# SPI.net
KiCad netlist of a schematic drawn in Altium Designer
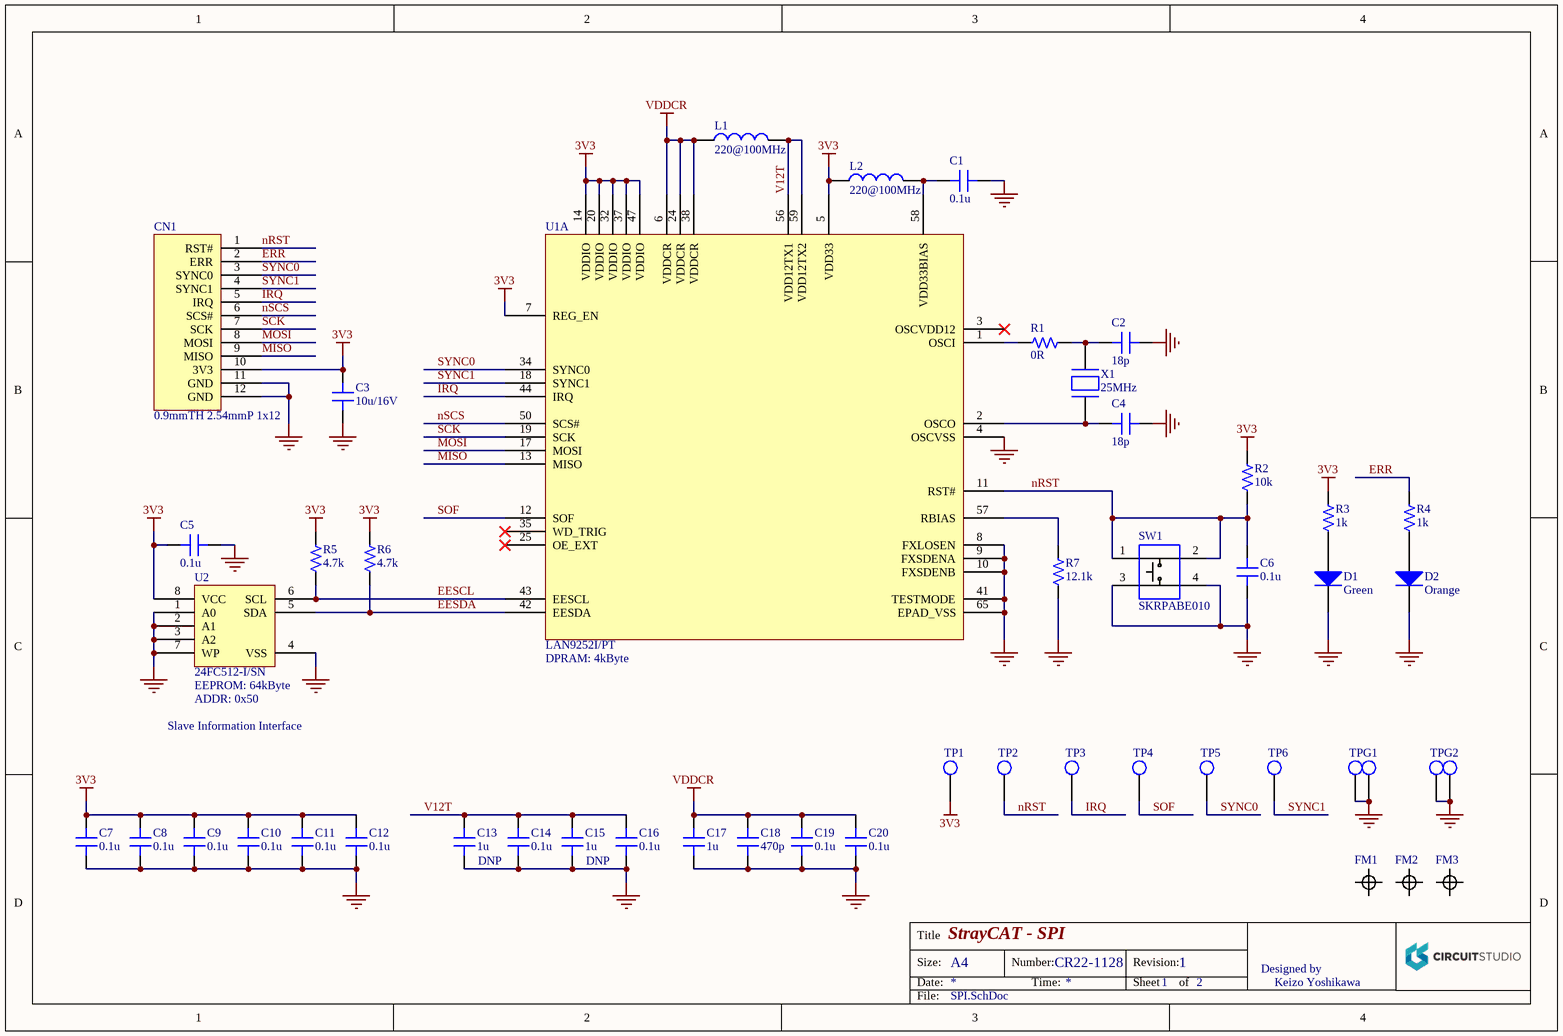
[diagram p0: SPI.SchDoc]

(export (version "E")
  (design (tool "Eeschema 10.0.6"))
  (components
    (comp (ref "C1")
      (value "0.1u")
      (footprint "CGA3")
      (description "1608 0.1uF 50V X7R 10%")
      (libsource (lib "CGA3") (part "CGA3E2X7R1H104K080AA"))
    )
    (comp (ref "C2")
      (value "18p")
      (footprint "CGA3")
      (description "1608 18pF 50V C0G 5%")
      (libsource (lib "CGA3") (part "CGA3E2C0G1H180J080AA"))
    )
    (comp (ref "C3")
      (value "10u/16V")
      (footprint "CGA4")
      (description "2012 10uF 16V X5R 10%")
      (libsource (lib "CGA4") (part "CGA4J1X5R1C106K125AC"))
    )
    (comp (ref "C4")
      (value "18p")
      (footprint "CGA3")
      (description "1608 18pF 50V C0G 5%")
      (libsource (lib "CGA3") (part "CGA3E2C0G1H180J080AA"))
    )
    (comp (ref "C5")
      (value "0.1u")
      (footprint "CGA3")
      (description "1608 0.1uF 50V X7R 10%")
      (libsource (lib "CGA3") (part "CGA3E2X7R1H104K080AA"))
    )
    (comp (ref "C6")
      (value "0.1u")
      (footprint "CGA3")
      (description "1608 0.1uF 50V X7R 10%")
      (libsource (lib "CGA3") (part "CGA3E2X7R1H104K080AA"))
    )
    (comp (ref "C7")
      (value "0.1u")
      (footprint "CGA3")
      (description "1608 0.1uF 50V X7R 10%")
      (libsource (lib "CGA3") (part "CGA3E2X7R1H104K080AA"))
    )
    (comp (ref "C8")
      (value "0.1u")
      (footprint "CGA3")
      (description "1608 0.1uF 50V X7R 10%")
      (libsource (lib "CGA3") (part "CGA3E2X7R1H104K080AA"))
    )
    (comp (ref "C9")
      (value "0.1u")
      (footprint "CGA3")
      (description "1608 0.1uF 50V X7R 10%")
      (libsource (lib "CGA3") (part "CGA3E2X7R1H104K080AA"))
    )
    (comp (ref "C10")
      (value "0.1u")
      (footprint "CGA3")
      (description "1608 0.1uF 50V X7R 10%")
      (libsource (lib "CGA3") (part "CGA3E2X7R1H104K080AA"))
    )
    (comp (ref "C11")
      (value "0.1u")
      (footprint "CGA3")
      (description "1608 0.1uF 50V X7R 10%")
      (libsource (lib "CGA3") (part "CGA3E2X7R1H104K080AA"))
    )
    (comp (ref "C12")
      (value "0.1u")
      (footprint "CGA3")
      (description "1608 0.1uF 50V X7R 10%")
      (libsource (lib "CGA3") (part "CGA3E2X7R1H104K080AA"))
    )
    (comp (ref "C13")
      (value "1u")
      (footprint "CGA3")
      (description "1608 1uF 25V X7R 10%")
      (libsource (lib "CGA3") (part "CGA3E1X7R1E105K080AC"))
    )
    (comp (ref "C14")
      (value "0.1u")
      (footprint "CGA3")
      (description "1608 0.1uF 50V X7R 10%")
      (libsource (lib "CGA3") (part "CGA3E2X7R1H104K080AA"))
    )
    (comp (ref "C15")
      (value "1u")
      (footprint "CGA3")
      (description "1608 1uF 25V X7R 10%")
      (libsource (lib "CGA3") (part "CGA3E1X7R1E105K080AC"))
    )
    (comp (ref "C16")
      (value "0.1u")
      (footprint "CGA3")
      (description "1608 0.1uF 50V X7R 10%")
      (libsource (lib "CGA3") (part "CGA3E2X7R1H104K080AA"))
    )
    (comp (ref "C17")
      (value "1u")
      (footprint "CGA3")
      (description "1608 1uF 25V X7R 10%")
      (libsource (lib "CGA3") (part "CGA3E1X7R1E105K080AC"))
    )
    (comp (ref "C18")
      (value "470p")
      (footprint "CGA3")
      (description "1608 470pF 50V C0G 5%")
      (libsource (lib "CGA3") (part "CGA3E2C0G1H471J080AA"))
    )
    (comp (ref "C19")
      (value "0.1u")
      (footprint "CGA3")
      (description "1608 0.1uF 50V X7R 10%")
      (libsource (lib "CGA3") (part "CGA3E2X7R1H104K080AA"))
    )
    (comp (ref "C20")
      (value "0.1u")
      (footprint "CGA3")
      (description "1608 0.1uF 50V X7R 10%")
      (libsource (lib "CGA3") (part "CGA3E2X7R1H104K080AA"))
    )
    (comp (ref "CN1")
      (value "0.9mmTH 2.54mmP 1x12")
      (footprint "61301211121")
      (description "WR-PHD Pin Header 12pin")
      (libsource (lib "61301211121") (part "61301211121"))
    )
    (comp (ref "D1")
      (value "Green")
      (footprint "DIOC2012X08N")
      (description "2012 Chip LED Green")
      (libsource (lib "APT2012") (part "APT2012QGW"))
    )
    (comp (ref "D2")
      (value "Orange")
      (footprint "DIOC2012X08N")
      (description "2012 Chip LED Orange")
      (libsource (lib "APT2012") (part "APT2012NW"))
    )
    (comp (ref "FM1")
      (value "FIDUCIAL_MARK")
      (footprint "Fiducial Mark")
      (libsource (lib "FIDUCIAL_MARK") (part "FIDUCIAL_MARK"))
    )
    (comp (ref "FM2")
      (value "FIDUCIAL_MARK")
      (footprint "Fiducial Mark")
      (libsource (lib "FIDUCIAL_MARK") (part "FIDUCIAL_MARK"))
    )
    (comp (ref "FM3")
      (value "FIDUCIAL_MARK")
      (footprint "Fiducial Mark")
      (libsource (lib "FIDUCIAL_MARK") (part "FIDUCIAL_MARK"))
    )
    (comp (ref "L1")
      (value "220@100MHz")
      (footprint "BLM18EG221SN1D")
      (description "Noise Suppression Chip Ferrite Bead")
      (libsource (lib "BLM18EG221SN1D") (part "BLM18EG221SN1D"))
    )
    (comp (ref "L2")
      (value "220@100MHz")
      (footprint "BLM18EG221SN1D")
      (description "Noise Suppression Chip Ferrite Bead")
      (libsource (lib "BLM18EG221SN1D") (part "BLM18EG221SN1D"))
    )
    (comp (ref "R1")
      (value "0R")
      (footprint "RK73x1J")
      (description "1608 0-Ohm 1A")
      (libsource (lib "RK73X1J") (part "RK73Z1JTTD"))
    )
    (comp (ref "R2")
      (value "10k")
      (footprint "RK73x1J")
      (description "1608 10kOhm 5% 1/10W")
      (libsource (lib "RK73X1J") (part "RK73B1JTTD103J"))
    )
    (comp (ref "R3")
      (value "1k")
      (footprint "RK73x1J")
      (description "1608 1kOhm 5% 1/8W")
      (libsource (lib "RK73X1J") (part "RK73B1JTTD102J"))
    )
    (comp (ref "R4")
      (value "1k")
      (footprint "RK73x1J")
      (description "1608 1kOhm 5% 1/8W")
      (libsource (lib "RK73X1J") (part "RK73B1JTTD102J"))
    )
    (comp (ref "R5")
      (value "4.7k")
      (footprint "RK73x1J")
      (description "1608 4.7kOhm 5% 1/10W")
      (libsource (lib "RK73X1J") (part "RK73B1JTTD472J"))
    )
    (comp (ref "R6")
      (value "4.7k")
      (footprint "RK73x1J")
      (description "1608 4.7kOhm 5% 1/10W")
      (libsource (lib "RK73X1J") (part "RK73B1JTTD472J"))
    )
    (comp (ref "R7")
      (value "12.1k")
      (footprint "RK73x1J")
      (description "1608 12.1kOhm 1% 1/10W")
      (libsource (lib "RK73X1J") (part "RK73H1JTTD1212F"))
    )
    (comp (ref "SW1")
      (value "SKRPABE010")
      (footprint "SKRPABE010")
      (description "SPST Switch N/O 1.57N")
      (libsource (lib "SKRPABE010") (part "SKRPABE010"))
    )
    (comp (ref "TP1")
      (value "3V3")
      (footprint "TEST_POINT")
      (description "0.9mmH Through-Hole")
      (libsource (lib "TEST_POINT") (part "TEST_POINT"))
    )
    (comp (ref "TP2")
      (value "nRST")
      (footprint "TEST_POINT")
      (description "0.9mmH Through-Hole")
      (libsource (lib "TEST_POINT") (part "TEST_POINT"))
    )
    (comp (ref "TP3")
      (value "IRQ")
      (footprint "TEST_POINT")
      (description "0.9mmH Through-Hole")
      (libsource (lib "TEST_POINT") (part "TEST_POINT"))
    )
    (comp (ref "TP4")
      (value "SOF")
      (footprint "TEST_POINT")
      (description "0.9mmH Through-Hole")
      (libsource (lib "TEST_POINT") (part "TEST_POINT"))
    )
    (comp (ref "TP5")
      (value "SYNC0")
      (footprint "TEST_POINT")
      (description "0.9mmH Through-Hole")
      (libsource (lib "TEST_POINT") (part "TEST_POINT"))
    )
    (comp (ref "TP6")
      (value "SYNC1")
      (footprint "TEST_POINT")
      (description "0.9mmH Through-Hole")
      (libsource (lib "TEST_POINT") (part "TEST_POINT"))
    )
    (comp (ref "TPG1")
      (value "TEST_POINT2")
      (footprint "TEST_POINT2")
      (description "0.9mmH Through-Hole")
      (libsource (lib "TEST_POINT") (part "TEST_POINT2"))
    )
    (comp (ref "TPG2")
      (value "TEST_POINT2")
      (footprint "TEST_POINT2")
      (description "0.9mmH Through-Hole")
      (libsource (lib "TEST_POINT") (part "TEST_POINT2"))
    )
    (comp (ref "U1")
      (value "LAN9252I/PT")
      (footprint "TSQFP50P1200X1200X105_HS-65N")
      (description "EtherCAT Slave Controller")
      (libsource (lib "LAN9252I_PT") (part "LAN9252I_PT"))
    )
    (comp (ref "U2")
      (value "24FC512-I/SN")
      (footprint "24FC512-I_SN")
      (description "512kBit I2C Serial EEPROM")
      (libsource (lib "24FC512-I_SN") (part "24FC512-I_SN"))
    )
    (comp (ref "X1")
      (value "25MHz")
      (footprint "CSM1Z-A5B2C5-40-25_0D18-F")
      (description "HC-49S 25MHz Crystal")
      (libsource (lib "CSM1Z-A5B2C5-40-25_0D18-F") (part "CSM1Z-A5B2C5-40-25_0D18-F"))
    )
  )
  (nets
    (net (code "1") (name "/EESCL") (class "Default")
      (node (ref "R5") (pin "2") (pinfunction "2_2") (pintype "passive"))
      (node (ref "U1") (pin "43") (pinfunction "EESCL_43") (pintype "passive"))
      (node (ref "U2") (pin "6") (pinfunction "SCL_6") (pintype "passive"))
    )
    (net (code "2") (name "/EESDA") (class "Default")
      (node (ref "R6") (pin "2") (pinfunction "2_2") (pintype "passive"))
      (node (ref "U1") (pin "42") (pinfunction "EESDA_42") (pintype "passive"))
      (node (ref "U2") (pin "5") (pinfunction "SDA_5") (pintype "passive"))
    )
    (net (code "3") (name "/ERR") (class "Default")
      (node (ref "CN1") (pin "2") (pinfunction "ERR_2") (pintype "passive"))
      (node (ref "R4") (pin "1") (pinfunction "1_1") (pintype "passive"))
    )
    (net (code "4") (name "/IRQ") (class "Default")
      (node (ref "CN1") (pin "5") (pinfunction "IRQ_5") (pintype "passive"))
      (node (ref "TP3") (pin "1") (pinfunction "1_1") (pintype "passive"))
      (node (ref "U1") (pin "44") (pinfunction "IRQ_44") (pintype "passive"))
    )
    (net (code "5") (name "/MISO") (class "Default")
      (node (ref "CN1") (pin "9") (pinfunction "MISO_9") (pintype "passive"))
      (node (ref "U1") (pin "13") (pinfunction "MISO_13") (pintype "passive"))
    )
    (net (code "6") (name "/MOSI") (class "Default")
      (node (ref "CN1") (pin "8") (pinfunction "MOSI_8") (pintype "passive"))
      (node (ref "U1") (pin "17") (pinfunction "MOSI_17") (pintype "passive"))
    )
    (net (code "7") (name "/SCK") (class "Default")
      (node (ref "CN1") (pin "7") (pinfunction "SCK_7") (pintype "passive"))
      (node (ref "U1") (pin "19") (pinfunction "SCK_19") (pintype "passive"))
    )
    (net (code "8") (name "/SOF") (class "Default")
      (node (ref "TP4") (pin "1") (pinfunction "1_1") (pintype "passive"))
      (node (ref "U1") (pin "12") (pinfunction "SOF_12") (pintype "passive"))
    )
    (net (code "9") (name "/SYNC0") (class "Default")
      (node (ref "CN1") (pin "3") (pinfunction "SYNC0_3") (pintype "passive"))
      (node (ref "TP5") (pin "1") (pinfunction "1_1") (pintype "passive"))
      (node (ref "U1") (pin "34") (pinfunction "SYNC0_34") (pintype "passive"))
    )
    (net (code "10") (name "/SYNC1") (class "Default")
      (node (ref "CN1") (pin "4") (pinfunction "SYNC1_4") (pintype "passive"))
      (node (ref "TP6") (pin "1") (pinfunction "1_1") (pintype "passive"))
      (node (ref "U1") (pin "18") (pinfunction "SYNC1_18") (pintype "passive"))
    )
    (net (code "11") (name "/V12T") (class "Default")
      (node (ref "C13") (pin "1") (pinfunction "1_1") (pintype "passive"))
      (node (ref "C14") (pin "1") (pinfunction "1_1") (pintype "passive"))
      (node (ref "C15") (pin "1") (pinfunction "1_1") (pintype "passive"))
      (node (ref "C16") (pin "1") (pinfunction "1_1") (pintype "passive"))
      (node (ref "L1") (pin "2") (pinfunction "2_2") (pintype "passive"))
      (node (ref "U1") (pin "56") (pinfunction "VDD12TX1_56") (pintype "passive"))
      (node (ref "U1") (pin "59") (pinfunction "VDD12TX2_59") (pintype "passive"))
    )
    (net (code "12") (name "/nRST") (class "Default")
      (node (ref "C6") (pin "1") (pinfunction "1_1") (pintype "passive"))
      (node (ref "CN1") (pin "1") (pinfunction "RST#_1") (pintype "passive"))
      (node (ref "R2") (pin "2") (pinfunction "2_2") (pintype "passive"))
      (node (ref "SW1") (pin "1") (pinfunction "1_1") (pintype "passive"))
      (node (ref "SW1") (pin "2") (pinfunction "2_2") (pintype "passive"))
      (node (ref "TP2") (pin "1") (pinfunction "1_1") (pintype "passive"))
      (node (ref "U1") (pin "11") (pinfunction "RST#_11") (pintype "passive"))
    )
    (net (code "13") (name "/nSCS") (class "Default")
      (node (ref "CN1") (pin "6") (pinfunction "SCS#_6") (pintype "passive"))
      (node (ref "U1") (pin "50") (pinfunction "SCS#_50") (pintype "passive"))
    )
    (net (code "14") (name "3V3") (class "Default")
      (node (ref "C10") (pin "1") (pinfunction "1_1") (pintype "passive"))
      (node (ref "C11") (pin "1") (pinfunction "1_1") (pintype "passive"))
      (node (ref "C12") (pin "1") (pinfunction "1_1") (pintype "passive"))
      (node (ref "C3") (pin "1") (pinfunction "1_1") (pintype "passive"))
      (node (ref "C5") (pin "1") (pinfunction "1_1") (pintype "passive"))
      (node (ref "C7") (pin "1") (pinfunction "1_1") (pintype "passive"))
      (node (ref "C8") (pin "1") (pinfunction "1_1") (pintype "passive"))
      (node (ref "C9") (pin "1") (pinfunction "1_1") (pintype "passive"))
      (node (ref "CN1") (pin "10") (pinfunction "3V3_10") (pintype "passive"))
      (node (ref "L2") (pin "1") (pinfunction "1_1") (pintype "passive"))
      (node (ref "R2") (pin "1") (pinfunction "1_1") (pintype "passive"))
      (node (ref "R3") (pin "1") (pinfunction "1_1") (pintype "passive"))
      (node (ref "R5") (pin "1") (pinfunction "1_1") (pintype "passive"))
      (node (ref "R6") (pin "1") (pinfunction "1_1") (pintype "passive"))
      (node (ref "TP1") (pin "1") (pinfunction "1_1") (pintype "passive"))
      (node (ref "U1") (pin "14") (pinfunction "VDDIO_14") (pintype "passive"))
      (node (ref "U1") (pin "20") (pinfunction "VDDIO_20") (pintype "passive"))
      (node (ref "U1") (pin "32") (pinfunction "VDDIO_32") (pintype "passive"))
      (node (ref "U1") (pin "37") (pinfunction "VDDIO_37") (pintype "passive"))
      (node (ref "U1") (pin "47") (pinfunction "VDDIO_47") (pintype "passive"))
      (node (ref "U1") (pin "5") (pinfunction "VDD33_5") (pintype "passive"))
      (node (ref "U1") (pin "7") (pinfunction "REG_EN_7") (pintype "passive"))
      (node (ref "U2") (pin "8") (pinfunction "VCC_8") (pintype "passive"))
    )
    (net (code "15") (name "GND") (class "Default")
      (node (ref "C1") (pin "2") (pinfunction "2_2") (pintype "passive"))
      (node (ref "C10") (pin "2") (pinfunction "2_2") (pintype "passive"))
      (node (ref "C11") (pin "2") (pinfunction "2_2") (pintype "passive"))
      (node (ref "C12") (pin "2") (pinfunction "2_2") (pintype "passive"))
      (node (ref "C13") (pin "2") (pinfunction "2_2") (pintype "passive"))
      (node (ref "C14") (pin "2") (pinfunction "2_2") (pintype "passive"))
      (node (ref "C15") (pin "2") (pinfunction "2_2") (pintype "passive"))
      (node (ref "C16") (pin "2") (pinfunction "2_2") (pintype "passive"))
      (node (ref "C17") (pin "2") (pinfunction "2_2") (pintype "passive"))
      (node (ref "C18") (pin "2") (pinfunction "2_2") (pintype "passive"))
      (node (ref "C19") (pin "2") (pinfunction "2_2") (pintype "passive"))
      (node (ref "C2") (pin "2") (pinfunction "2_2") (pintype "passive"))
      (node (ref "C20") (pin "2") (pinfunction "2_2") (pintype "passive"))
      (node (ref "C3") (pin "2") (pinfunction "2_2") (pintype "passive"))
      (node (ref "C4") (pin "2") (pinfunction "2_2") (pintype "passive"))
      (node (ref "C5") (pin "2") (pinfunction "2_2") (pintype "passive"))
      (node (ref "C6") (pin "2") (pinfunction "2_2") (pintype "passive"))
      (node (ref "C7") (pin "2") (pinfunction "2_2") (pintype "passive"))
      (node (ref "C8") (pin "2") (pinfunction "2_2") (pintype "passive"))
      (node (ref "C9") (pin "2") (pinfunction "2_2") (pintype "passive"))
      (node (ref "CN1") (pin "11") (pinfunction "GND_11") (pintype "passive"))
      (node (ref "CN1") (pin "12") (pinfunction "GND_12") (pintype "passive"))
      (node (ref "D1") (pin "2") (pinfunction "K_2") (pintype "passive"))
      (node (ref "D2") (pin "2") (pinfunction "K_2") (pintype "passive"))
      (node (ref "R7") (pin "2") (pinfunction "2_2") (pintype "passive"))
      (node (ref "SW1") (pin "3") (pinfunction "3_3") (pintype "passive"))
      (node (ref "SW1") (pin "4") (pinfunction "4_4") (pintype "passive"))
      (node (ref "TPG1") (pin "1") (pinfunction "1_1") (pintype "passive"))
      (node (ref "TPG1") (pin "2") (pinfunction "2_2") (pintype "passive"))
      (node (ref "TPG2") (pin "1") (pinfunction "1_1") (pintype "passive"))
      (node (ref "TPG2") (pin "2") (pinfunction "2_2") (pintype "passive"))
      (node (ref "U1") (pin "10") (pinfunction "FXSDENB_10") (pintype "passive"))
      (node (ref "U1") (pin "4") (pinfunction "OSCVSS_4") (pintype "passive"))
      (node (ref "U1") (pin "41") (pinfunction "TESTMODE_41") (pintype "passive"))
      (node (ref "U1") (pin "65") (pinfunction "EPAD_VSS_65") (pintype "passive"))
      (node (ref "U1") (pin "8") (pinfunction "FXLOSEN_8") (pintype "passive"))
      (node (ref "U1") (pin "9") (pinfunction "FXSDENA_9") (pintype "passive"))
      (node (ref "U2") (pin "1") (pinfunction "A0_1") (pintype "passive"))
      (node (ref "U2") (pin "2") (pinfunction "A1_2") (pintype "passive"))
      (node (ref "U2") (pin "3") (pinfunction "A2_3") (pintype "passive"))
      (node (ref "U2") (pin "4") (pinfunction "VSS_4") (pintype "passive"))
      (node (ref "U2") (pin "7") (pinfunction "WP_7") (pintype "passive"))
    )
    (net (code "16") (name "Net-(C2-Pad1)") (class "Default")
      (node (ref "C2") (pin "1") (pinfunction "1_1") (pintype "passive"))
      (node (ref "R1") (pin "2") (pinfunction "2_2") (pintype "passive"))
      (node (ref "X1") (pin "1") (pinfunction "1_1") (pintype "passive"))
    )
    (net (code "17") (name "Net-(D1-A)") (class "Default")
      (node (ref "D1") (pin "1") (pinfunction "A_1") (pintype "passive"))
      (node (ref "R3") (pin "2") (pinfunction "2_2") (pintype "passive"))
    )
    (net (code "18") (name "Net-(D2-A)") (class "Default")
      (node (ref "D2") (pin "1") (pinfunction "A_1") (pintype "passive"))
      (node (ref "R4") (pin "2") (pinfunction "2_2") (pintype "passive"))
    )
    (net (code "19") (name "Net-(U1A-OSCI)") (class "Default")
      (node (ref "R1") (pin "1") (pinfunction "1_1") (pintype "passive"))
      (node (ref "U1") (pin "1") (pinfunction "OSCI_1") (pintype "passive"))
    )
    (net (code "20") (name "Net-(U1A-OSCO)") (class "Default")
      (node (ref "C4") (pin "1") (pinfunction "1_1") (pintype "passive"))
      (node (ref "U1") (pin "2") (pinfunction "OSCO_2") (pintype "passive"))
      (node (ref "X1") (pin "2") (pinfunction "2_2") (pintype "passive"))
    )
    (net (code "21") (name "Net-(U1A-RBIAS)") (class "Default")
      (node (ref "R7") (pin "1") (pinfunction "1_1") (pintype "passive"))
      (node (ref "U1") (pin "57") (pinfunction "RBIAS_57") (pintype "passive"))
    )
    (net (code "22") (name "Net-(U1A-VDD33BIAS)") (class "Default")
      (node (ref "C1") (pin "1") (pinfunction "1_1") (pintype "passive"))
      (node (ref "L2") (pin "2") (pinfunction "2_2") (pintype "passive"))
      (node (ref "U1") (pin "58") (pinfunction "VDD33BIAS_58") (pintype "passive"))
    )
    (net (code "23") (name "VDDCR") (class "Default")
      (node (ref "C17") (pin "1") (pinfunction "1_1") (pintype "passive"))
      (node (ref "C18") (pin "1") (pinfunction "1_1") (pintype "passive"))
      (node (ref "C19") (pin "1") (pinfunction "1_1") (pintype "passive"))
      (node (ref "C20") (pin "1") (pinfunction "1_1") (pintype "passive"))
      (node (ref "L1") (pin "1") (pinfunction "1_1") (pintype "passive"))
      (node (ref "U1") (pin "24") (pinfunction "VDDCR_24") (pintype "passive"))
      (node (ref "U1") (pin "38") (pinfunction "VDDCR_38") (pintype "passive"))
      (node (ref "U1") (pin "6") (pinfunction "VDDCR_6") (pintype "passive"))
    )
    (net (code "24") (name "unconnected-(U1A-OE_EXT-Pad25)") (class "Default")
      (node (ref "U1") (pin "25") (pinfunction "OE_EXT_25") (pintype "passive+no_connect"))
    )
    (net (code "25") (name "unconnected-(U1A-OSCVDD12-Pad3)") (class "Default")
      (node (ref "U1") (pin "3") (pinfunction "OSCVDD12_3") (pintype "passive+no_connect"))
    )
    (net (code "26") (name "unconnected-(U1A-WD_TRIG-Pad35)") (class "Default")
      (node (ref "U1") (pin "35") (pinfunction "WD_TRIG_35") (pintype "passive+no_connect"))
    )
  )
)
